# AutomaticPlantWatering.net
KiCad netlist of a schematic drawn in EAGLE
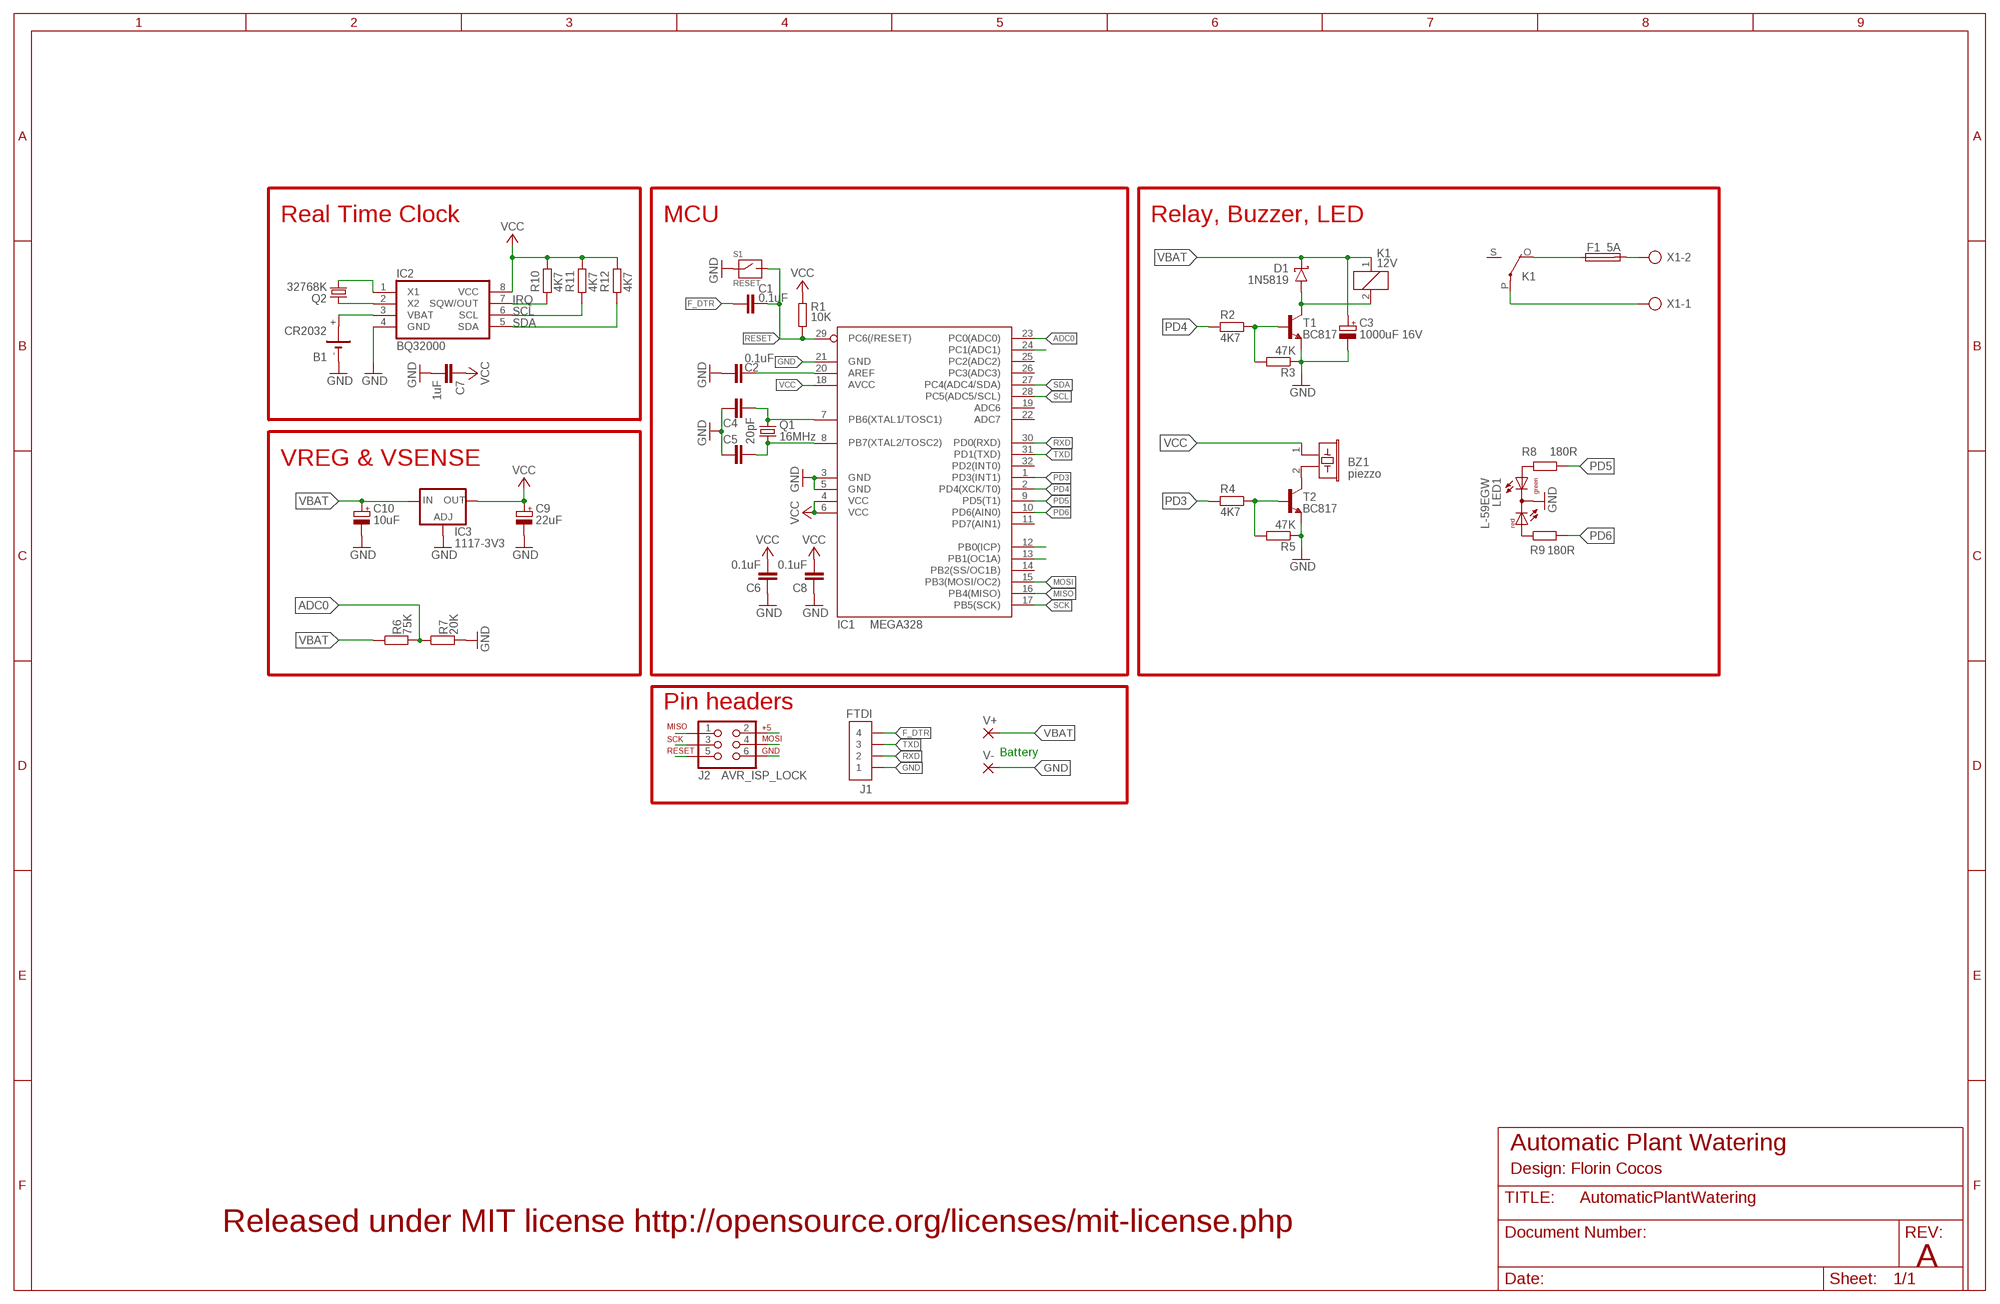
[diagram p0: schematic, sheet 1]

(export (version "E")
  (design (tool "Eeschema 10.0.6"))
  (components
    (comp (ref "B1")
      (value "CR2032")
      (footprint "eagle-import:CR2032H")
      (libsource (lib "eagle-import") (part "CR2032H"))
    )
    (comp (ref "BZ1")
      (value "piezzo")
      (footprint "eagle-import:EFBAA40D101")
      (libsource (lib "eagle-import") (part "EFB?AA40D101"))
    )
    (comp (ref "C1")
      (value "0.1uF")
      (footprint "eagle-import:C0805")
      (libsource (lib "eagle-import") (part "C-EUC0805"))
    )
    (comp (ref "C2")
      (value "0.1uF")
      (footprint "eagle-import:C0805")
      (libsource (lib "eagle-import") (part "C-EUC0805"))
    )
    (comp (ref "C3")
      (value "1000uF 16V")
      (footprint "eagle-import:CPOL-5.5X10.5")
      (libsource (lib "eagle-import") (part "CAPACITOR-CPOL-5.5X10.5"))
    )
    (comp (ref "C4")
      (value "20pF")
      (footprint "eagle-import:C0805")
      (libsource (lib "eagle-import") (part "C-EUC0805"))
    )
    (comp (ref "C5")
      (value "20pF")
      (footprint "eagle-import:C0805")
      (libsource (lib "eagle-import") (part "C-EUC0805"))
    )
    (comp (ref "C6")
      (value "0.1uF")
      (footprint "eagle-import:C0805")
      (libsource (lib "eagle-import") (part "C-EUC0805"))
    )
    (comp (ref "C7")
      (value "1uF")
      (footprint "eagle-import:C0805")
      (libsource (lib "eagle-import") (part "C-EUC0805"))
    )
    (comp (ref "C8")
      (value "0.1uF")
      (footprint "eagle-import:C0805")
      (libsource (lib "eagle-import") (part "C-EUC0805"))
    )
    (comp (ref "C9")
      (value "22uF")
      (footprint "eagle-import:CPOL-5.5X10.5")
      (libsource (lib "eagle-import") (part "CAPACITOR-CPOL-5.5X10.5"))
    )
    (comp (ref "C10")
      (value "10uF")
      (footprint "eagle-import:CPOL-5.5X10.5")
      (libsource (lib "eagle-import") (part "CAPACITOR-CPOL-5.5X10.5"))
    )
    (comp (ref "D1")
      (value "1N5819")
      (footprint "eagle-import:SMA")
      (libsource (lib "eagle-import") (part "DIODE-SCHOTTKY-SMA"))
    )
    (comp (ref "F1")
      (value "5A")
      (footprint "eagle-import:SH22,5A")
      (libsource (lib "eagle-import") (part "FUSESH22,5A"))
    )
    (comp (ref "IC1")
      (value "MEGA328")
      (footprint "eagle-import:TQFP32-08")
      (libsource (lib "eagle-import") (part "MEGA8-AI"))
    )
    (comp (ref "IC2")
      (value "BQ32000")
      (footprint "eagle-import:SO-8")
      (libsource (lib "eagle-import") (part "IC_RTC_DS1307"))
    )
    (comp (ref "IC3")
      (value "1117-3V3")
      (footprint "eagle-import:SOT223")
      (libsource (lib "eagle-import") (part "LD117A?S12TR"))
    )
    (comp (ref "J1")
      (value "FTDI")
      (footprint "eagle-import:1X4_LOCK")
      (libsource (lib "eagle-import") (part "1X4_LOCK"))
    )
    (comp (ref "J2")
      (value "AVR_ISP_LOCK")
      (footprint "eagle-import:2X3_LOCK")
      (libsource (lib "eagle-import") (part "AVR_ISP_LOCK"))
    )
    (comp (ref "K1")
      (value "12V")
      (footprint "eagle-import:ZF112")
      (libsource (lib "eagle-import") (part "ZF112"))
    )
    (comp (ref "LED1")
      (value "L-59EGW")
      (footprint "eagle-import:DUOLED-C-5MM")
      (libsource (lib "eagle-import") (part "DUOLED-RG-C"))
    )
    (comp (ref "Q1")
      (value "16MHz")
      (footprint "eagle-import:SM49")
      (libsource (lib "eagle-import") (part "CRYSTALSM49"))
    )
    (comp (ref "Q2")
      (value "32768K")
      (footprint "eagle-import:SM49")
      (libsource (lib "eagle-import") (part "CRYSTALSM49"))
    )
    (comp (ref "R1")
      (value "10K")
      (footprint "eagle-import:R0805")
      (libsource (lib "eagle-import") (part "R-EU_R0805"))
    )
    (comp (ref "R2")
      (value "4K7")
      (footprint "eagle-import:R0805")
      (libsource (lib "eagle-import") (part "R-EU_R0805"))
    )
    (comp (ref "R3")
      (value "47K")
      (footprint "eagle-import:R0805")
      (libsource (lib "eagle-import") (part "R-EU_R0805"))
    )
    (comp (ref "R4")
      (value "4K7")
      (footprint "eagle-import:R0805")
      (libsource (lib "eagle-import") (part "R-EU_R0805"))
    )
    (comp (ref "R5")
      (value "47K")
      (footprint "eagle-import:R0805")
      (libsource (lib "eagle-import") (part "R-EU_R0805"))
    )
    (comp (ref "R6")
      (value "75K")
      (footprint "eagle-import:R0805")
      (libsource (lib "eagle-import") (part "R-EU_R0805"))
    )
    (comp (ref "R7")
      (value "20K")
      (footprint "eagle-import:R0805")
      (libsource (lib "eagle-import") (part "R-EU_R0805"))
    )
    (comp (ref "R8")
      (value "180R")
      (footprint "eagle-import:R0805")
      (libsource (lib "eagle-import") (part "R-EU_R0805"))
    )
    (comp (ref "R9")
      (value "180R")
      (footprint "eagle-import:R0805")
      (libsource (lib "eagle-import") (part "R-EU_R0805"))
    )
    (comp (ref "R10")
      (value "4K7")
      (footprint "eagle-import:R0805")
      (libsource (lib "eagle-import") (part "R-EU_R0805"))
    )
    (comp (ref "R11")
      (value "4K7")
      (footprint "eagle-import:R0805")
      (libsource (lib "eagle-import") (part "R-EU_R0805"))
    )
    (comp (ref "R12")
      (value "4K7")
      (footprint "eagle-import:R0805")
      (libsource (lib "eagle-import") (part "R-EU_R0805"))
    )
    (comp (ref "S1")
      (value "RESET")
      (footprint "eagle-import:SWITCH-SMT-3.7X6.2")
      (libsource (lib "eagle-import") (part "SWITCH-SMT"))
    )
    (comp (ref "T1")
      (value "BC817")
      (footprint "eagle-import:SOT23-BEC")
      (libsource (lib "eagle-import") (part "-NPN-SOT23-BECBC817-40"))
    )
    (comp (ref "T2")
      (value "BC817")
      (footprint "eagle-import:SOT23-BEC")
      (libsource (lib "eagle-import") (part "-NPN-SOT23-BECBC817-40"))
    )
    (comp (ref "V+")
      (value "SMD5")
      (footprint "eagle-import:SMD2,54-5,08")
      (libsource (lib "eagle-import") (part "SMD5"))
    )
    (comp (ref "V-")
      (value "SMD5")
      (footprint "eagle-import:SMD2,54-5,08")
      (libsource (lib "eagle-import") (part "SMD5"))
    )
    (comp (ref "X1")
      (value "AK500/2")
      (footprint "eagle-import:AK500_2")
      (libsource (lib "eagle-import") (part "AK500/2"))
    )
  )
  (nets
    (net (code "1") (name "/IRQ") (class "Default")
      (node (ref "IC2") (pin "7") (pinfunction "SQW/OUT_7") (pintype "bidirectional"))
      (node (ref "R10") (pin "2") (pinfunction "2_2") (pintype "passive"))
    )
    (net (code "2") (name "ADC0") (class "Default")
      (node (ref "IC1") (pin "23") (pinfunction "PC0(ADC0)_23") (pintype "bidirectional"))
      (node (ref "R6") (pin "2") (pinfunction "2_2") (pintype "passive"))
      (node (ref "R7") (pin "1") (pinfunction "1_1") (pintype "passive"))
    )
    (net (code "3") (name "F_DTR") (class "Default")
      (node (ref "C1") (pin "1") (pinfunction "1_1") (pintype "passive"))
      (node (ref "J1") (pin "4") (pinfunction "4_4") (pintype "bidirectional"))
    )
    (net (code "4") (name "GND") (class "Default")
      (node (ref "B1") (pin "-") (pinfunction "-_-") (pintype "passive"))
      (node (ref "C10") (pin "N") (pinfunction "NEGATIVE_N") (pintype "bidirectional"))
      (node (ref "C2") (pin "1") (pinfunction "1_1") (pintype "passive"))
      (node (ref "C3") (pin "N") (pinfunction "NEGATIVE_N") (pintype "bidirectional"))
      (node (ref "C4") (pin "1") (pinfunction "1_1") (pintype "passive"))
      (node (ref "C5") (pin "1") (pinfunction "1_1") (pintype "passive"))
      (node (ref "C6") (pin "1") (pinfunction "1_1") (pintype "passive"))
      (node (ref "C7") (pin "2") (pinfunction "2_2") (pintype "passive"))
      (node (ref "C8") (pin "1") (pinfunction "1_1") (pintype "passive"))
      (node (ref "C9") (pin "N") (pinfunction "NEGATIVE_N") (pintype "bidirectional"))
      (node (ref "IC1") (pin "21") (pinfunction "GND_21") (pintype "power_in"))
      (node (ref "IC1") (pin "3") (pinfunction "GND_3") (pintype "power_in"))
      (node (ref "IC1") (pin "5") (pinfunction "GND_5") (pintype "power_in"))
      (node (ref "IC2") (pin "4") (pinfunction "GND_4") (pintype "bidirectional"))
      (node (ref "IC3") (pin "1") (pinfunction "ADJ_1") (pintype "input"))
      (node (ref "J1") (pin "1") (pinfunction "1_1") (pintype "bidirectional"))
      (node (ref "J2") (pin "6") (pinfunction "6_6") (pintype "passive"))
      (node (ref "LED1") (pin "C") (pinfunction "C_C") (pintype "passive"))
      (node (ref "R3") (pin "1") (pinfunction "1_1") (pintype "passive"))
      (node (ref "R5") (pin "1") (pinfunction "1_1") (pintype "passive"))
      (node (ref "R7") (pin "2") (pinfunction "2_2") (pintype "passive"))
      (node (ref "S1") (pin "1") (pinfunction "P$1_1") (pintype "bidirectional"))
      (node (ref "T1") (pin "E") (pinfunction "E_E") (pintype "passive"))
      (node (ref "T2") (pin "E") (pinfunction "E_E") (pintype "passive"))
      (node (ref "V-") (pin "1") (pinfunction "P_1") (pintype "passive"))
    )
    (net (code "5") (name "MISO") (class "Default")
      (node (ref "IC1") (pin "16") (pinfunction "PB4(MISO)_16") (pintype "bidirectional"))
      (node (ref "J2") (pin "1") (pinfunction "1_1") (pintype "passive"))
    )
    (net (code "6") (name "MOSI") (class "Default")
      (node (ref "IC1") (pin "15") (pinfunction "PB3(MOSI/OC2)_15") (pintype "bidirectional"))
      (node (ref "J2") (pin "4") (pinfunction "4_4") (pintype "passive"))
    )
    (net (code "7") (name "Net-(BZ1-Pad2)") (class "Default")
      (node (ref "BZ1") (pin "2") (pinfunction "2_2") (pintype "passive"))
      (node (ref "T2") (pin "C") (pinfunction "C_C") (pintype "passive"))
    )
    (net (code "8") (name "Net-(D1-PadA)") (class "Default")
      (node (ref "D1") (pin "A") (pinfunction "A_A") (pintype "bidirectional"))
      (node (ref "K1") (pin "2") (pinfunction "2_2") (pintype "passive"))
      (node (ref "T1") (pin "C") (pinfunction "C_C") (pintype "passive"))
    )
    (net (code "9") (name "Net-(F1-Pad1)") (class "Default")
      (node (ref "F1") (pin "1") (pinfunction "1_1") (pintype "passive"))
      (node (ref "K1") (pin "O") (pinfunction "O_O") (pintype "passive"))
    )
    (net (code "10") (name "Net-(IC1-AREF)") (class "Default")
      (node (ref "C2") (pin "2") (pinfunction "2_2") (pintype "passive"))
      (node (ref "IC1") (pin "20") (pinfunction "AREF_20") (pintype "passive"))
    )
    (net (code "11") (name "Net-(IC1-PB6(XTAL1{slash}TOSC1))") (class "Default")
      (node (ref "C4") (pin "2") (pinfunction "2_2") (pintype "passive"))
      (node (ref "IC1") (pin "7") (pinfunction "PB6(XTAL1/TOSC1)_7") (pintype "bidirectional"))
      (node (ref "Q1") (pin "1") (pinfunction "1_1") (pintype "passive"))
    )
    (net (code "12") (name "Net-(IC1-PB7(XTAL2{slash}TOSC2))") (class "Default")
      (node (ref "C5") (pin "2") (pinfunction "2_2") (pintype "passive"))
      (node (ref "IC1") (pin "8") (pinfunction "PB7(XTAL2/TOSC2)_8") (pintype "bidirectional"))
      (node (ref "Q1") (pin "2") (pinfunction "2_2") (pintype "passive"))
    )
    (net (code "13") (name "Net-(IC2-VBAT)") (class "Default")
      (node (ref "B1") (pin "+") (pinfunction "+_+") (pintype "passive"))
      (node (ref "IC2") (pin "3") (pinfunction "VBAT_3") (pintype "bidirectional"))
    )
    (net (code "14") (name "Net-(IC2-X1)") (class "Default")
      (node (ref "IC2") (pin "1") (pinfunction "X1_1") (pintype "bidirectional"))
      (node (ref "Q2") (pin "2") (pinfunction "2_2") (pintype "passive"))
    )
    (net (code "15") (name "Net-(IC2-X2)") (class "Default")
      (node (ref "IC2") (pin "2") (pinfunction "X2_2") (pintype "bidirectional"))
      (node (ref "Q2") (pin "1") (pinfunction "1_1") (pintype "passive"))
    )
    (net (code "16") (name "Net-(LED1-AG)") (class "Default")
      (node (ref "LED1") (pin "AX") (pinfunction "AG_AX") (pintype "passive"))
      (node (ref "R8") (pin "2") (pinfunction "2_2") (pintype "passive"))
    )
    (net (code "17") (name "Net-(LED1-PadAR)") (class "Default")
      (node (ref "LED1") (pin "AR") (pinfunction "AR_AR") (pintype "passive"))
      (node (ref "R9") (pin "1") (pinfunction "1_1") (pintype "passive"))
    )
    (net (code "18") (name "Net-(R2-Pad1)") (class "Default")
      (node (ref "R2") (pin "1") (pinfunction "1_1") (pintype "passive"))
      (node (ref "R3") (pin "2") (pinfunction "2_2") (pintype "passive"))
      (node (ref "T1") (pin "B") (pinfunction "B_B") (pintype "passive"))
    )
    (net (code "19") (name "Net-(R4-Pad1)") (class "Default")
      (node (ref "R4") (pin "1") (pinfunction "1_1") (pintype "passive"))
      (node (ref "R5") (pin "2") (pinfunction "2_2") (pintype "passive"))
      (node (ref "T2") (pin "B") (pinfunction "B_B") (pintype "passive"))
    )
    (net (code "20") (name "Net-(X1A-KL)") (class "Default")
      (node (ref "K1") (pin "P") (pinfunction "P_P") (pintype "passive"))
      (node (ref "X1") (pin "1") (pinfunction "KL_1") (pintype "passive"))
    )
    (net (code "21") (name "Net-(X1B-KL)") (class "Default")
      (node (ref "F1") (pin "2") (pinfunction "2_2") (pintype "passive"))
      (node (ref "X1") (pin "2") (pinfunction "KL_2") (pintype "passive"))
    )
    (net (code "22") (name "PD3") (class "Default")
      (node (ref "IC1") (pin "1") (pinfunction "PD3(INT1)_1") (pintype "bidirectional"))
      (node (ref "R4") (pin "2") (pinfunction "2_2") (pintype "passive"))
    )
    (net (code "23") (name "PD4") (class "Default")
      (node (ref "IC1") (pin "2") (pinfunction "PD4(XCK/T0)_2") (pintype "bidirectional"))
      (node (ref "R2") (pin "2") (pinfunction "2_2") (pintype "passive"))
    )
    (net (code "24") (name "PD5") (class "Default")
      (node (ref "IC1") (pin "9") (pinfunction "PD5(T1)_9") (pintype "bidirectional"))
      (node (ref "R8") (pin "1") (pinfunction "1_1") (pintype "passive"))
    )
    (net (code "25") (name "PD6") (class "Default")
      (node (ref "IC1") (pin "10") (pinfunction "PD6(AIN0)_10") (pintype "bidirectional"))
      (node (ref "R9") (pin "2") (pinfunction "2_2") (pintype "passive"))
    )
    (net (code "26") (name "RESET") (class "Default")
      (node (ref "C1") (pin "2") (pinfunction "2_2") (pintype "passive"))
      (node (ref "IC1") (pin "29") (pinfunction "PC6(/RESET)_29") (pintype "bidirectional"))
      (node (ref "J2") (pin "5") (pinfunction "5_5") (pintype "passive"))
      (node (ref "R1") (pin "1") (pinfunction "1_1") (pintype "passive"))
      (node (ref "S1") (pin "2") (pinfunction "P$2_2") (pintype "bidirectional"))
    )
    (net (code "27") (name "RXD") (class "Default")
      (node (ref "IC1") (pin "30") (pinfunction "PD0(RXD)_30") (pintype "bidirectional"))
      (node (ref "J1") (pin "2") (pinfunction "2_2") (pintype "bidirectional"))
    )
    (net (code "28") (name "SCK") (class "Default")
      (node (ref "IC1") (pin "17") (pinfunction "PB5(SCK)_17") (pintype "bidirectional"))
      (node (ref "J2") (pin "3") (pinfunction "3_3") (pintype "passive"))
    )
    (net (code "29") (name "SCL") (class "Default")
      (node (ref "IC1") (pin "28") (pinfunction "PC5(ADC5/SCL)_28") (pintype "bidirectional"))
      (node (ref "IC2") (pin "6") (pinfunction "SCL_6") (pintype "bidirectional"))
      (node (ref "R11") (pin "2") (pinfunction "2_2") (pintype "passive"))
    )
    (net (code "30") (name "SDA") (class "Default")
      (node (ref "IC1") (pin "27") (pinfunction "PC4(ADC4/SDA)_27") (pintype "bidirectional"))
      (node (ref "IC2") (pin "5") (pinfunction "SDA_5") (pintype "bidirectional"))
      (node (ref "R12") (pin "2") (pinfunction "2_2") (pintype "passive"))
    )
    (net (code "31") (name "TXD") (class "Default")
      (node (ref "IC1") (pin "31") (pinfunction "PD1(TXD)_31") (pintype "bidirectional"))
      (node (ref "J1") (pin "3") (pinfunction "3_3") (pintype "bidirectional"))
    )
    (net (code "32") (name "VBAT") (class "Default")
      (node (ref "C10") (pin "P") (pinfunction "POSITIVE_P") (pintype "bidirectional"))
      (node (ref "C3") (pin "P") (pinfunction "POSITIVE_P") (pintype "bidirectional"))
      (node (ref "D1") (pin "K") (pinfunction "K_K") (pintype "bidirectional"))
      (node (ref "IC3") (pin "3") (pinfunction "IN_3") (pintype "input"))
      (node (ref "K1") (pin "1") (pinfunction "1_1") (pintype "passive"))
      (node (ref "R6") (pin "1") (pinfunction "1_1") (pintype "passive"))
      (node (ref "V+") (pin "1") (pinfunction "P_1") (pintype "passive"))
    )
    (net (code "33") (name "VCC") (class "Default")
      (node (ref "BZ1") (pin "1") (pinfunction "1_1") (pintype "passive"))
      (node (ref "C6") (pin "2") (pinfunction "2_2") (pintype "passive"))
      (node (ref "C7") (pin "1") (pinfunction "1_1") (pintype "passive"))
      (node (ref "C8") (pin "2") (pinfunction "2_2") (pintype "passive"))
      (node (ref "C9") (pin "P") (pinfunction "POSITIVE_P") (pintype "bidirectional"))
      (node (ref "IC1") (pin "18") (pinfunction "AVCC_18") (pintype "power_in"))
      (node (ref "IC1") (pin "4") (pinfunction "VCC_4") (pintype "power_in"))
      (node (ref "IC1") (pin "6") (pinfunction "VCC_6") (pintype "power_in"))
      (node (ref "IC2") (pin "8") (pinfunction "VCC_8") (pintype "bidirectional"))
      (node (ref "IC3") (pin "4") (pinfunction "OUT_4") (pintype "passive"))
      (node (ref "J2") (pin "2") (pinfunction "2_2") (pintype "passive"))
      (node (ref "R1") (pin "2") (pinfunction "2_2") (pintype "passive"))
      (node (ref "R10") (pin "1") (pinfunction "1_1") (pintype "passive"))
      (node (ref "R11") (pin "1") (pinfunction "1_1") (pintype "passive"))
      (node (ref "R12") (pin "1") (pinfunction "1_1") (pintype "passive"))
    )
    (net (code "34") (name "unconnected-(B1-+-Pad+@1)") (class "Default")
      (node (ref "B1") (pin "+@1") (pinfunction "+_+@1") (pintype "passive"))
    )
    (net (code "35") (name "unconnected-(IC1-ADC6-Pad19)") (class "Default")
      (node (ref "IC1") (pin "19") (pinfunction "ADC6_19") (pintype "bidirectional"))
    )
    (net (code "36") (name "unconnected-(IC1-ADC7-Pad22)") (class "Default")
      (node (ref "IC1") (pin "22") (pinfunction "ADC7_22") (pintype "bidirectional"))
    )
    (net (code "37") (name "unconnected-(IC1-PB0(ICP)-Pad12)") (class "Default")
      (node (ref "IC1") (pin "12") (pinfunction "PB0(ICP)_12") (pintype "bidirectional"))
    )
    (net (code "38") (name "unconnected-(IC1-PB1(OC1A)-Pad13)") (class "Default")
      (node (ref "IC1") (pin "13") (pinfunction "PB1(OC1A)_13") (pintype "bidirectional"))
    )
    (net (code "39") (name "unconnected-(IC1-PB2(SS{slash}OC1B)-Pad14)") (class "Default")
      (node (ref "IC1") (pin "14") (pinfunction "PB2(SS/OC1B)_14") (pintype "bidirectional"))
    )
    (net (code "40") (name "unconnected-(IC1-PC1(ADC1)-Pad24)") (class "Default")
      (node (ref "IC1") (pin "24") (pinfunction "PC1(ADC1)_24") (pintype "bidirectional"))
    )
    (net (code "41") (name "unconnected-(IC1-PC2(ADC2)-Pad25)") (class "Default")
      (node (ref "IC1") (pin "25") (pinfunction "PC2(ADC2)_25") (pintype "bidirectional"))
    )
    (net (code "42") (name "unconnected-(IC1-PC3(ADC3)-Pad26)") (class "Default")
      (node (ref "IC1") (pin "26") (pinfunction "PC3(ADC3)_26") (pintype "bidirectional"))
    )
    (net (code "43") (name "unconnected-(IC1-PD2(INT0)-Pad32)") (class "Default")
      (node (ref "IC1") (pin "32") (pinfunction "PD2(INT0)_32") (pintype "bidirectional"))
    )
    (net (code "44") (name "unconnected-(IC1-PD7(AIN1)-Pad11)") (class "Default")
      (node (ref "IC1") (pin "11") (pinfunction "PD7(AIN1)_11") (pintype "bidirectional"))
    )
    (net (code "45") (name "unconnected-(K1-PadS)") (class "Default")
      (node (ref "K1") (pin "S") (pinfunction "S_S") (pintype "passive"))
    )
  )
)
